# AmbaSat-04-OPT3001.net
KiCad netlist of a schematic drawn in EAGLE
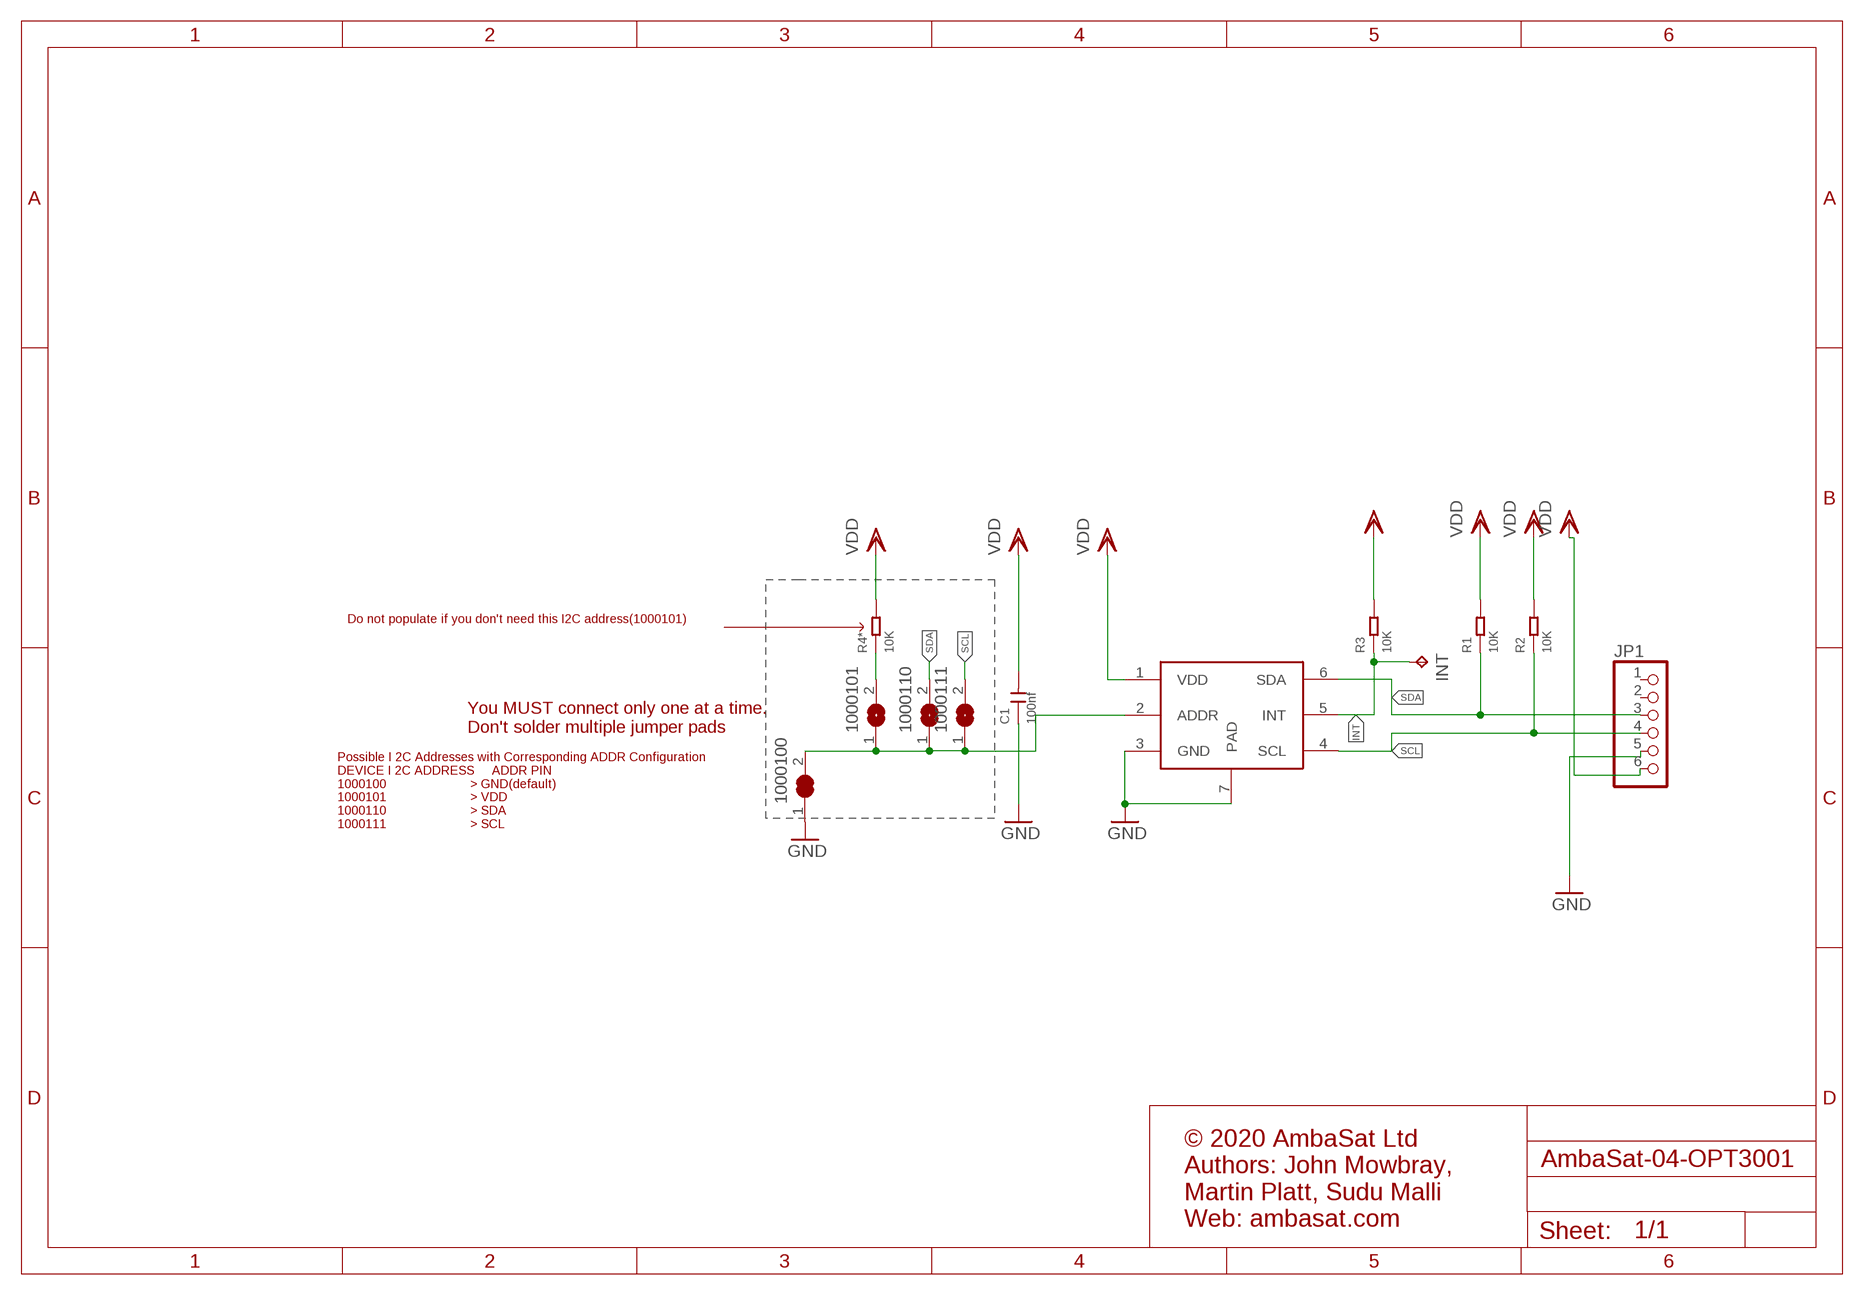
[diagram p0: schematic, sheet 1]

(export (version "E")
  (design (tool "Eeschema 10.0.6"))
  (components
    (comp (ref "1000100")
      (value "SOLDERJUMPER_CLOSED")
      (footprint "eagle-import:SOLDERJUMPER_CLOSEDWIRE")
      (libsource (lib "eagle-import") (part "SOLDERJUMPER_CLOSED"))
    )
    (comp (ref "1000101")
      (value "SJ")
      (footprint "eagle-import:SJ")
      (libsource (lib "eagle-import") (part "SJ"))
    )
    (comp (ref "1000110")
      (value "SJ")
      (footprint "eagle-import:SJ")
      (libsource (lib "eagle-import") (part "SJ"))
    )
    (comp (ref "1000111")
      (value "SJ")
      (footprint "eagle-import:SJ")
      (libsource (lib "eagle-import") (part "SJ"))
    )
    (comp (ref "C1")
      (value "100nf")
      (footprint "eagle-import:C0805")
      (fields (field (name "MPN") "CC0805KRX7R9BB104"))
      (libsource (lib "eagle-import") (part "CERAMIC-100NF-50V-10%-X7R(0805)"))
    )
    (comp (ref "INT")
      (value "TPTP11R")
      (footprint "eagle-import:TP11R")
      (libsource (lib "eagle-import") (part "TPTP11R"))
    )
    (comp (ref "JP1")
      (value "HEADER-1X6")
      (footprint "eagle-import:1X06_OVAL")
      (libsource (lib "eagle-import") (part "HEADER-1X6"))
    )
    (comp (ref "R1")
      (value "10K")
      (footprint "eagle-import:R0805")
      (fields (field (name "MPN") "RC0805FR-0710KL"))
      (libsource (lib "eagle-import") (part "SMD-RES-10K-1%-1/8W(0805)"))
    )
    (comp (ref "R2")
      (value "10K")
      (footprint "eagle-import:R0805")
      (fields (field (name "MPN") "RC0805FR-0710KL"))
      (libsource (lib "eagle-import") (part "SMD-RES-10K-1%-1/8W(0805)"))
    )
    (comp (ref "R3")
      (value "10K")
      (footprint "eagle-import:R0805")
      (fields (field (name "MPN") "RC0805FR-0710KL"))
      (libsource (lib "eagle-import") (part "SMD-RES-10K-1%-1/8W(0805)"))
    )
    (comp (ref "R4*")
      (value "10K")
      (footprint "eagle-import:R0805")
      (fields (field (name "MPN") "RC0805FR-0710KL"))
      (libsource (lib "eagle-import") (part "SMD-RES-10K-1%-1/8W(0805)"))
    )
    (comp (ref "U2")
      (value "OPT3001")
      (footprint "eagle-import:SON65P200X200X65-7N")
      (fields (field (name "MPN") "OPT3001DNPT"))
      (libsource (lib "eagle-import") (part "OPT3001"))
    )
  )
  (nets
    (net (code "1") (name "GND") (class "Default")
      (node (ref "1000100") (pin "1") (pinfunction "1_1") (pintype "passive"))
      (node (ref "C1") (pin "1") (pinfunction "1_1") (pintype "passive"))
      (node (ref "JP1") (pin "5") (pinfunction "5_5") (pintype "passive"))
      (node (ref "U2") (pin "3") (pinfunction "GND_3") (pintype "bidirectional"))
      (node (ref "U2") (pin "7") (pinfunction "PAD_7") (pintype "bidirectional"))
    )
    (net (code "2") (name "INT") (class "Default")
      (node (ref "INT") (pin "TP") (pinfunction "TP_TP") (pintype "input"))
      (node (ref "R3") (pin "1") (pinfunction "1_1") (pintype "passive"))
      (node (ref "U2") (pin "5") (pinfunction "INT_5") (pintype "bidirectional"))
    )
    (net (code "3") (name "Net-(1000101-Pad2)") (class "Default")
      (node (ref "1000101") (pin "2") (pinfunction "2_2") (pintype "passive"))
      (node (ref "R4*") (pin "1") (pinfunction "1_1") (pintype "passive"))
    )
    (net (code "4") (name "Net-(U2-ADDR)") (class "Default")
      (node (ref "1000100") (pin "2") (pinfunction "2_2") (pintype "passive"))
      (node (ref "1000101") (pin "1") (pinfunction "1_1") (pintype "passive"))
      (node (ref "1000110") (pin "1") (pinfunction "1_1") (pintype "passive"))
      (node (ref "1000111") (pin "1") (pinfunction "1_1") (pintype "passive"))
      (node (ref "U2") (pin "2") (pinfunction "ADDR_2") (pintype "bidirectional"))
    )
    (net (code "5") (name "SCL") (class "Default")
      (node (ref "1000111") (pin "2") (pinfunction "2_2") (pintype "passive"))
      (node (ref "JP1") (pin "4") (pinfunction "4_4") (pintype "passive"))
      (node (ref "R2") (pin "1") (pinfunction "1_1") (pintype "passive"))
      (node (ref "U2") (pin "4") (pinfunction "SCL_4") (pintype "bidirectional"))
    )
    (net (code "6") (name "SDA") (class "Default")
      (node (ref "1000110") (pin "2") (pinfunction "2_2") (pintype "passive"))
      (node (ref "JP1") (pin "3") (pinfunction "3_3") (pintype "passive"))
      (node (ref "R1") (pin "1") (pinfunction "1_1") (pintype "passive"))
      (node (ref "U2") (pin "6") (pinfunction "SDA_6") (pintype "bidirectional"))
    )
    (net (code "7") (name "VDD") (class "Default")
      (node (ref "C1") (pin "2") (pinfunction "2_2") (pintype "passive"))
      (node (ref "JP1") (pin "6") (pinfunction "6_6") (pintype "passive"))
      (node (ref "R1") (pin "2") (pinfunction "2_2") (pintype "passive"))
      (node (ref "R2") (pin "2") (pinfunction "2_2") (pintype "passive"))
      (node (ref "R3") (pin "2") (pinfunction "2_2") (pintype "passive"))
      (node (ref "R4*") (pin "2") (pinfunction "2_2") (pintype "passive"))
      (node (ref "U2") (pin "1") (pinfunction "VDD_1") (pintype "bidirectional"))
    )
    (net (code "8") (name "unconnected-(JP1-Pad1)") (class "Default")
      (node (ref "JP1") (pin "1") (pinfunction "1_1") (pintype "passive"))
    )
    (net (code "9") (name "unconnected-(JP1-Pad2)") (class "Default")
      (node (ref "JP1") (pin "2") (pinfunction "2_2") (pintype "passive"))
    )
  )
)
